# Mainboard.net
KiCad netlist of a schematic drawn in EAGLE
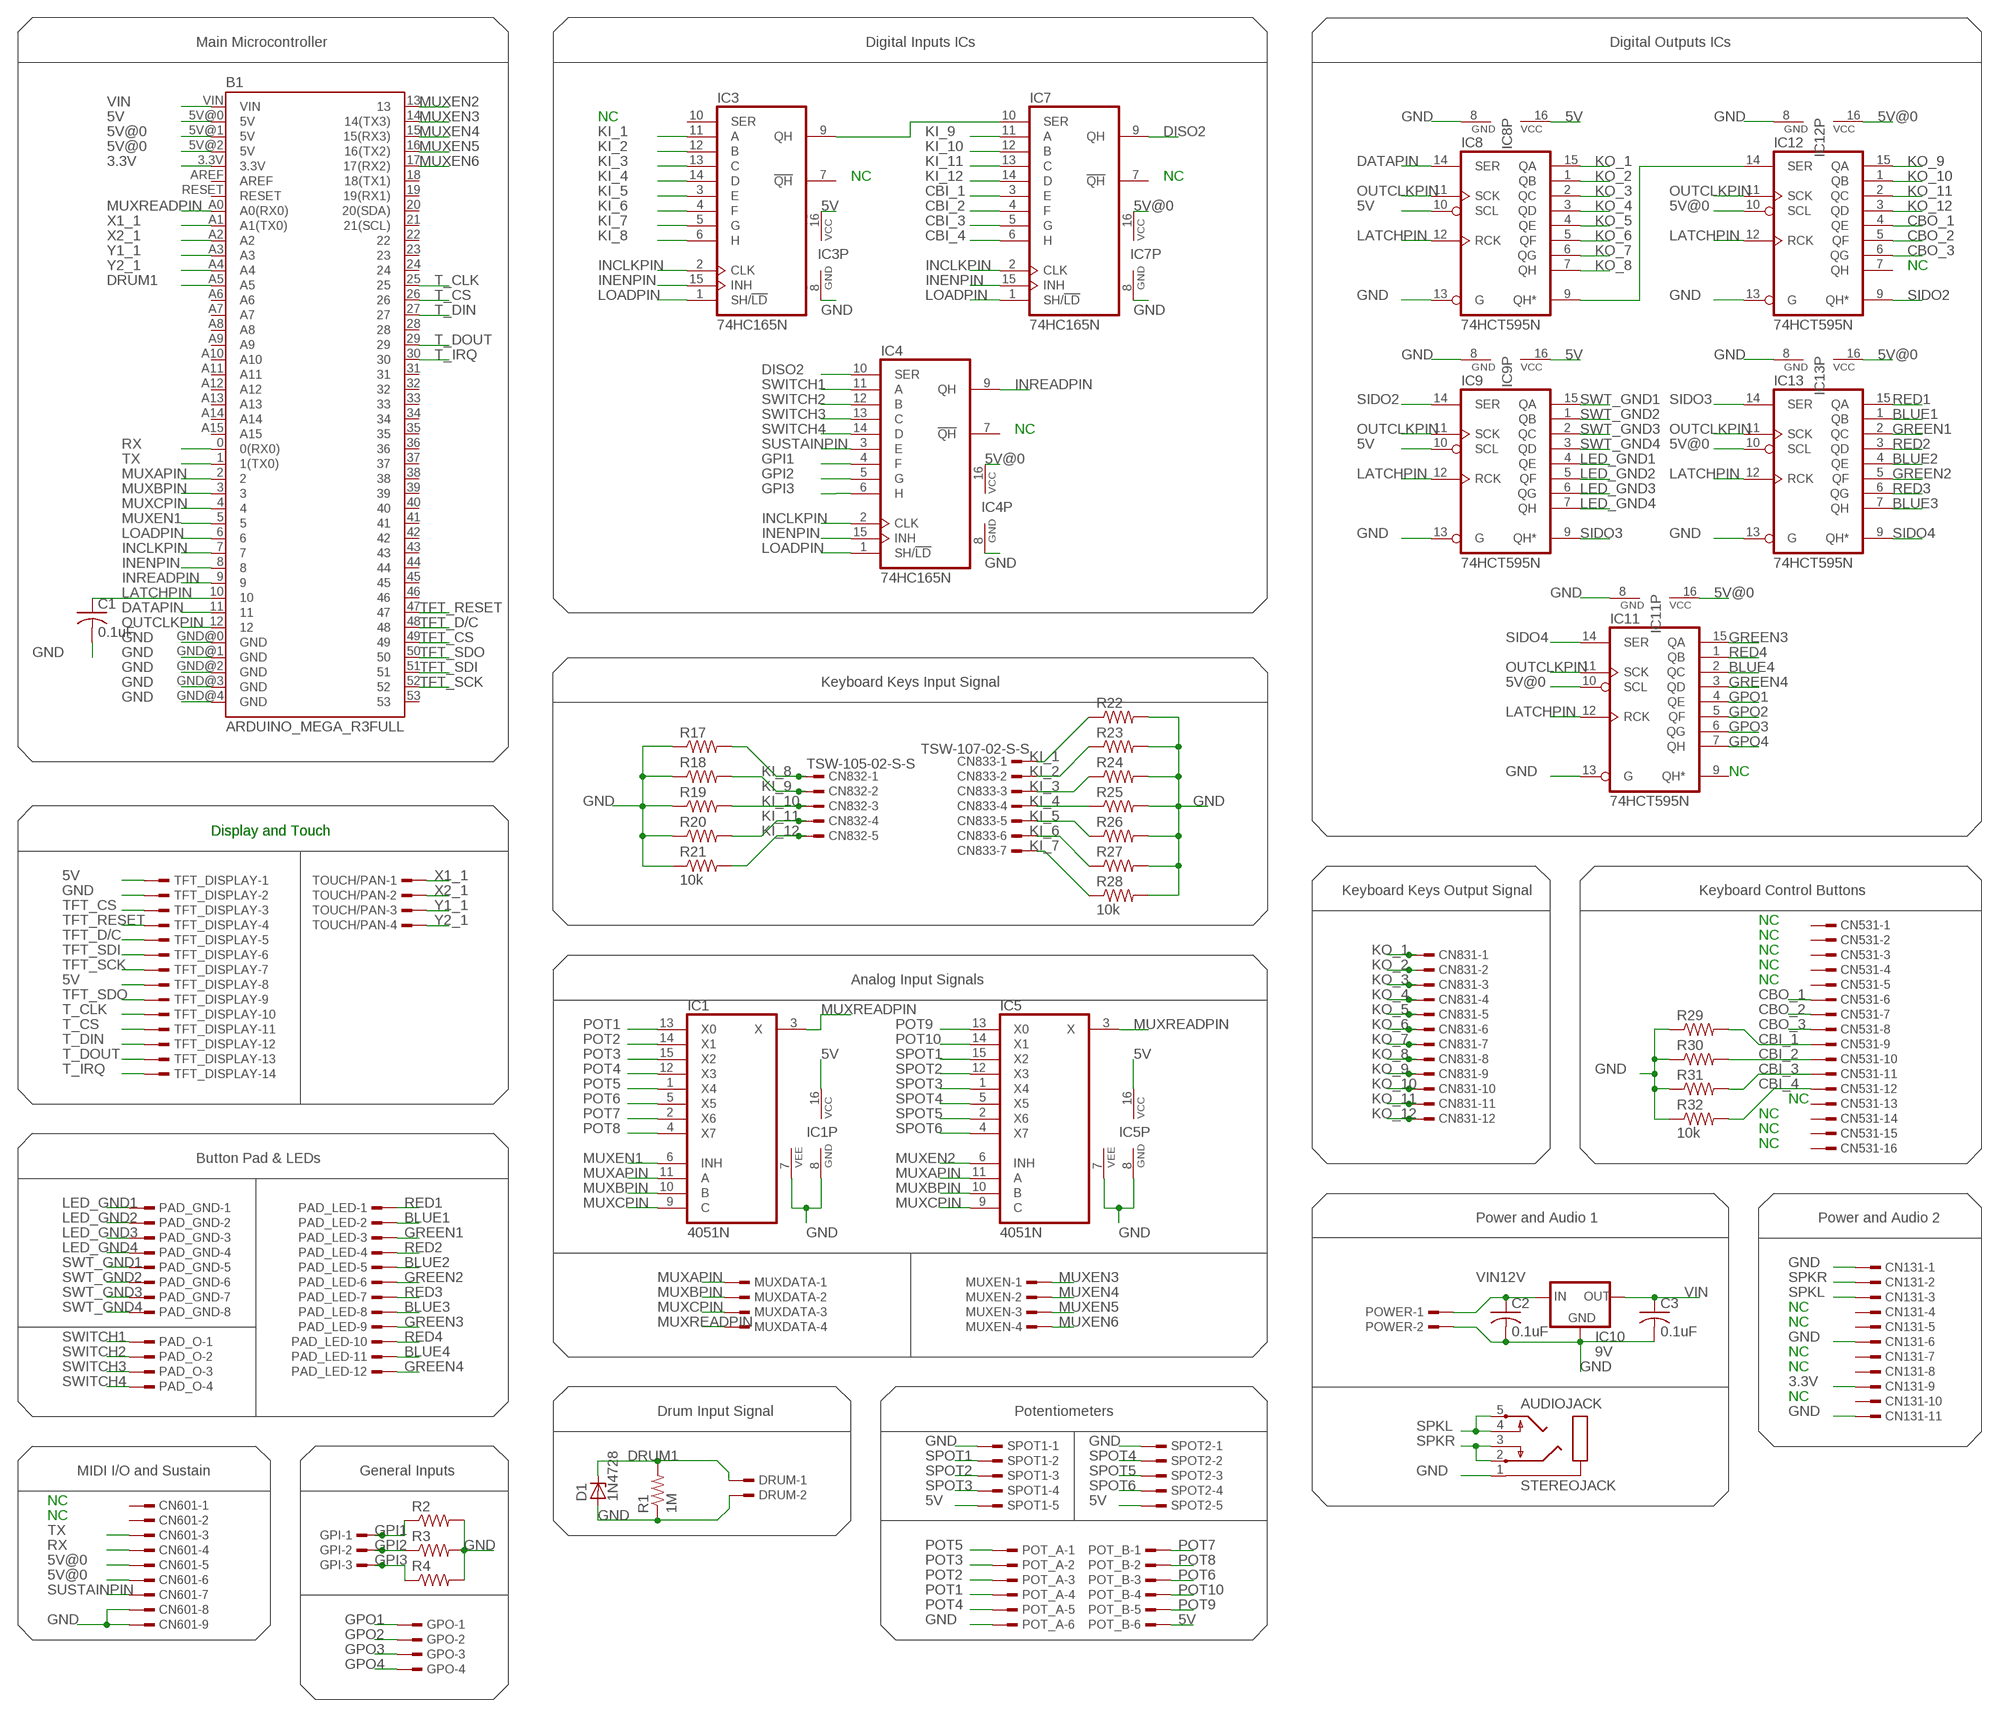
[diagram p0: schematic, sheet 1]

(export (version "E")
  (design (tool "Eeschema 10.0.6"))
  (components
    (comp (ref "AUDIOJACK")
      (value "STEREOJACK")
      (footprint "eagle-import:STX3100")
      (libsource (lib "eagle-import") (part "STEREOJACK"))
    )
    (comp (ref "B1")
      (value "ARDUINO_MEGA_R3FULL")
      (footprint "eagle-import:ARDUINO_MEGA")
      (libsource (lib "eagle-import") (part "ARDUINO_MEGA_R3FULL"))
    )
    (comp (ref "C1")
      (value "0.1uF")
      (footprint "eagle-import:C050-075X075")
      (libsource (lib "eagle-import") (part "C-US050-075X075"))
    )
    (comp (ref "C2")
      (value "0.1uF")
      (footprint "eagle-import:C050-075X075")
      (libsource (lib "eagle-import") (part "C-US050-075X075"))
    )
    (comp (ref "C3")
      (value "0.1uF")
      (footprint "eagle-import:C050-075X075")
      (libsource (lib "eagle-import") (part "C-US050-075X075"))
    )
    (comp (ref "CN131")
      (value "TSW-111-02-S-S")
      (footprint "eagle-import:TSW-111-02-S-S")
      (libsource (lib "eagle-import") (part "TSW-111-02-S-S"))
    )
    (comp (ref "CN531")
      (value "TSW-116-02-S-S")
      (footprint "eagle-import:TSW-116-02-S-S")
      (libsource (lib "eagle-import") (part "TSW-116-02-S-S"))
    )
    (comp (ref "CN601")
      (value "TSW-109-02-S-S")
      (footprint "eagle-import:TSW-109-02-S-S")
      (libsource (lib "eagle-import") (part "TSW-109-02-S-S"))
    )
    (comp (ref "CN831")
      (value "TSW-112-02-S-S")
      (footprint "eagle-import:TSW-112-02-S-S")
      (libsource (lib "eagle-import") (part "TSW-112-02-S-S"))
    )
    (comp (ref "CN832")
      (value "TSW-105-02-S-S")
      (footprint "eagle-import:TSW-105-02-S-S")
      (libsource (lib "eagle-import") (part "TSW-105-02-S-S"))
    )
    (comp (ref "CN833")
      (value "TSW-107-02-S-S")
      (footprint "eagle-import:TSW-107-02-S-S")
      (libsource (lib "eagle-import") (part "TSW-107-02-S-S"))
    )
    (comp (ref "D1")
      (value "1N4728")
      (footprint "eagle-import:DO41Z10")
      (libsource (lib "eagle-import") (part "1N4728"))
    )
    (comp (ref "DRUM")
      (value "TSW-102-02-S-S")
      (footprint "eagle-import:TSW-102-02-S-S")
      (libsource (lib "eagle-import") (part "TSW-102-02-S-S"))
    )
    (comp (ref "GPI")
      (value "TSW-103-02-S-S")
      (footprint "eagle-import:TSW-103-02-S-S")
      (libsource (lib "eagle-import") (part "TSW-103-02-S-S"))
    )
    (comp (ref "GPO")
      (value "TSW-104-02-S-S")
      (footprint "eagle-import:TSW-104-02-S-S")
      (libsource (lib "eagle-import") (part "TSW-104-02-S-S"))
    )
    (comp (ref "IC1")
      (value "4051N")
      (footprint "eagle-import:DIL16")
      (libsource (lib "eagle-import") (part "4051N"))
    )
    (comp (ref "IC3")
      (value "74HC165N")
      (footprint "eagle-import:DIL16")
      (libsource (lib "eagle-import") (part "74165NHC"))
    )
    (comp (ref "IC4")
      (value "74HC165N")
      (footprint "eagle-import:DIL16")
      (libsource (lib "eagle-import") (part "74165NHC"))
    )
    (comp (ref "IC5")
      (value "4051N")
      (footprint "eagle-import:DIL16")
      (libsource (lib "eagle-import") (part "4051N"))
    )
    (comp (ref "IC7")
      (value "74HC165N")
      (footprint "eagle-import:DIL16")
      (libsource (lib "eagle-import") (part "74165NHC"))
    )
    (comp (ref "IC8")
      (value "74HCT595N")
      (footprint "eagle-import:DIL16")
      (libsource (lib "eagle-import") (part "74595NHCT"))
    )
    (comp (ref "IC9")
      (value "74HCT595N")
      (footprint "eagle-import:DIL16")
      (libsource (lib "eagle-import") (part "74595NHCT"))
    )
    (comp (ref "IC10")
      (value "9V")
      (footprint "eagle-import:78XXL")
      (libsource (lib "eagle-import") (part "78XXL"))
    )
    (comp (ref "IC11")
      (value "74HCT595N")
      (footprint "eagle-import:DIL16")
      (libsource (lib "eagle-import") (part "74595NHCT"))
    )
    (comp (ref "IC12")
      (value "74HCT595N")
      (footprint "eagle-import:DIL16")
      (libsource (lib "eagle-import") (part "74595NHCT"))
    )
    (comp (ref "IC13")
      (value "74HCT595N")
      (footprint "eagle-import:DIL16")
      (libsource (lib "eagle-import") (part "74595NHCT"))
    )
    (comp (ref "MUXDATA")
      (value "TSW-104-02-S-S")
      (footprint "eagle-import:TSW-104-02-S-S")
      (libsource (lib "eagle-import") (part "TSW-104-02-S-S"))
    )
    (comp (ref "MUXEN")
      (value "TSW-104-02-S-S")
      (footprint "eagle-import:TSW-104-02-S-S")
      (libsource (lib "eagle-import") (part "TSW-104-02-S-S"))
    )
    (comp (ref "PAD_GND")
      (value "TSW-108-02-S-S")
      (footprint "eagle-import:TSW-108-02-S-S")
      (libsource (lib "eagle-import") (part "TSW-108-02-S-S"))
    )
    (comp (ref "PAD_LED")
      (value "TSW-112-02-S-S")
      (footprint "eagle-import:TSW-112-02-S-S")
      (libsource (lib "eagle-import") (part "TSW-112-02-S-S"))
    )
    (comp (ref "PAD_O")
      (value "TSW-104-02-S-S")
      (footprint "eagle-import:TSW-104-02-S-S")
      (libsource (lib "eagle-import") (part "TSW-104-02-S-S"))
    )
    (comp (ref "POT_A")
      (value "TSW-106-02-S-S")
      (footprint "eagle-import:TSW-106-02-S-S")
      (libsource (lib "eagle-import") (part "TSW-106-02-S-S"))
    )
    (comp (ref "POT_B")
      (value "TSW-106-02-S-S")
      (footprint "eagle-import:TSW-106-02-S-S")
      (libsource (lib "eagle-import") (part "TSW-106-02-S-S"))
    )
    (comp (ref "POWER")
      (value "TSW-102-02-S-S")
      (footprint "eagle-import:TSW-102-02-S-S")
      (libsource (lib "eagle-import") (part "TSW-102-02-S-S"))
    )
    (comp (ref "R1")
      (value "1M")
      (footprint "eagle-import:0309_12")
      (libsource (lib "eagle-import") (part "R-US_0309/12"))
    )
    (comp (ref "R2")
      (value "10k")
      (footprint "eagle-import:0309_12")
      (libsource (lib "eagle-import") (part "R-US_0309/12"))
    )
    (comp (ref "R3")
      (value "10k")
      (footprint "eagle-import:0309_12")
      (libsource (lib "eagle-import") (part "R-US_0309/12"))
    )
    (comp (ref "R4")
      (value "10k")
      (footprint "eagle-import:0309_12")
      (libsource (lib "eagle-import") (part "R-US_0309/12"))
    )
    (comp (ref "R17")
      (value "10k")
      (footprint "eagle-import:0309_12")
      (libsource (lib "eagle-import") (part "R-US_0309/12"))
    )
    (comp (ref "R18")
      (value "10k")
      (footprint "eagle-import:0309_12")
      (libsource (lib "eagle-import") (part "R-US_0309/12"))
    )
    (comp (ref "R19")
      (value "10k")
      (footprint "eagle-import:0309_12")
      (libsource (lib "eagle-import") (part "R-US_0309/12"))
    )
    (comp (ref "R20")
      (value "10k")
      (footprint "eagle-import:0309_12")
      (libsource (lib "eagle-import") (part "R-US_0309/12"))
    )
    (comp (ref "R21")
      (value "10k")
      (footprint "eagle-import:0309_12")
      (libsource (lib "eagle-import") (part "R-US_0309/12"))
    )
    (comp (ref "R22")
      (value "10k")
      (footprint "eagle-import:0309_12")
      (libsource (lib "eagle-import") (part "R-US_0309/12"))
    )
    (comp (ref "R23")
      (value "10k")
      (footprint "eagle-import:0309_12")
      (libsource (lib "eagle-import") (part "R-US_0309/12"))
    )
    (comp (ref "R24")
      (value "10k")
      (footprint "eagle-import:0309_12")
      (libsource (lib "eagle-import") (part "R-US_0309/12"))
    )
    (comp (ref "R25")
      (value "10k")
      (footprint "eagle-import:0309_12")
      (libsource (lib "eagle-import") (part "R-US_0309/12"))
    )
    (comp (ref "R26")
      (value "10k")
      (footprint "eagle-import:0309_12")
      (libsource (lib "eagle-import") (part "R-US_0309/12"))
    )
    (comp (ref "R27")
      (value "10k")
      (footprint "eagle-import:0309_12")
      (libsource (lib "eagle-import") (part "R-US_0309/12"))
    )
    (comp (ref "R28")
      (value "10k")
      (footprint "eagle-import:0309_12")
      (libsource (lib "eagle-import") (part "R-US_0309/12"))
    )
    (comp (ref "R29")
      (value "10k")
      (footprint "eagle-import:0309_12")
      (libsource (lib "eagle-import") (part "R-US_0309/12"))
    )
    (comp (ref "R30")
      (value "10k")
      (footprint "eagle-import:0309_12")
      (libsource (lib "eagle-import") (part "R-US_0309/12"))
    )
    (comp (ref "R31")
      (value "10k")
      (footprint "eagle-import:0309_12")
      (libsource (lib "eagle-import") (part "R-US_0309/12"))
    )
    (comp (ref "R32")
      (value "10k")
      (footprint "eagle-import:0309_12")
      (libsource (lib "eagle-import") (part "R-US_0309/12"))
    )
    (comp (ref "SPOT1")
      (value "TSW-105-02-S-S")
      (footprint "eagle-import:TSW-105-02-S-S")
      (libsource (lib "eagle-import") (part "TSW-105-02-S-S"))
    )
    (comp (ref "SPOT2")
      (value "TSW-105-02-S-S")
      (footprint "eagle-import:TSW-105-02-S-S")
      (libsource (lib "eagle-import") (part "TSW-105-02-S-S"))
    )
    (comp (ref "TFT_DISPLAY")
      (value "TSW-114-02-S-S")
      (footprint "eagle-import:TSW-114-02-S-S")
      (libsource (lib "eagle-import") (part "TSW-114-02-S-S"))
    )
    (comp (ref "TOUCH/PAN")
      (value "TSW-104-02-S-S")
      (footprint "eagle-import:TSW-104-02-S-S")
      (libsource (lib "eagle-import") (part "TSW-104-02-S-S"))
    )
  )
  (nets
    (net (code "1") (name "/3.3V") (class "Default")
      (node (ref "B1") (pin "3.3V") (pinfunction "3.3V_3.3V") (pintype "bidirectional"))
      (node (ref "CN131") (pin "9") (pinfunction "1_9") (pintype "passive"))
    )
    (net (code "2") (name "/5V") (class "Default")
      (node (ref "B1") (pin "5V@0") (pinfunction "5V_5V@0") (pintype "bidirectional"))
      (node (ref "IC1") (pin "16") (pinfunction "VCC_16") (pintype "power_in"))
      (node (ref "IC3") (pin "16") (pinfunction "VCC_16") (pintype "power_in"))
      (node (ref "IC5") (pin "16") (pinfunction "VCC_16") (pintype "power_in"))
      (node (ref "IC8") (pin "10") (pinfunction "SCL_10") (pintype "input"))
      (node (ref "IC8") (pin "16") (pinfunction "VCC_16") (pintype "power_in"))
      (node (ref "IC9") (pin "10") (pinfunction "SCL_10") (pintype "input"))
      (node (ref "IC9") (pin "16") (pinfunction "VCC_16") (pintype "power_in"))
      (node (ref "POT_B") (pin "6") (pinfunction "1_6") (pintype "passive"))
      (node (ref "SPOT1") (pin "5") (pinfunction "1_5") (pintype "passive"))
      (node (ref "SPOT2") (pin "5") (pinfunction "1_5") (pintype "passive"))
      (node (ref "TFT_DISPLAY") (pin "1") (pinfunction "1_1") (pintype "passive"))
      (node (ref "TFT_DISPLAY") (pin "8") (pinfunction "1_8") (pintype "passive"))
    )
    (net (code "3") (name "/5V@0") (class "Default")
      (node (ref "B1") (pin "5V@1") (pinfunction "5V_5V@1") (pintype "bidirectional"))
      (node (ref "B1") (pin "5V@2") (pinfunction "5V_5V@2") (pintype "bidirectional"))
      (node (ref "CN601") (pin "5") (pinfunction "1_5") (pintype "passive"))
      (node (ref "CN601") (pin "6") (pinfunction "1_6") (pintype "passive"))
      (node (ref "IC11") (pin "10") (pinfunction "SCL_10") (pintype "input"))
      (node (ref "IC11") (pin "16") (pinfunction "VCC_16") (pintype "power_in"))
      (node (ref "IC12") (pin "10") (pinfunction "SCL_10") (pintype "input"))
      (node (ref "IC12") (pin "16") (pinfunction "VCC_16") (pintype "power_in"))
      (node (ref "IC13") (pin "10") (pinfunction "SCL_10") (pintype "input"))
      (node (ref "IC13") (pin "16") (pinfunction "VCC_16") (pintype "power_in"))
      (node (ref "IC4") (pin "16") (pinfunction "VCC_16") (pintype "power_in"))
      (node (ref "IC7") (pin "16") (pinfunction "VCC_16") (pintype "power_in"))
    )
    (net (code "4") (name "/BLUE1") (class "Default")
      (node (ref "IC13") (pin "1") (pinfunction "QB_1") (pintype "tri_state"))
      (node (ref "PAD_LED") (pin "2") (pinfunction "1_2") (pintype "passive"))
    )
    (net (code "5") (name "/BLUE2") (class "Default")
      (node (ref "IC13") (pin "4") (pinfunction "QE_4") (pintype "tri_state"))
      (node (ref "PAD_LED") (pin "5") (pinfunction "1_5") (pintype "passive"))
    )
    (net (code "6") (name "/BLUE3") (class "Default")
      (node (ref "IC13") (pin "7") (pinfunction "QH_7") (pintype "tri_state"))
      (node (ref "PAD_LED") (pin "8") (pinfunction "1_8") (pintype "passive"))
    )
    (net (code "7") (name "/BLUE4") (class "Default")
      (node (ref "IC11") (pin "2") (pinfunction "QC_2") (pintype "tri_state"))
      (node (ref "PAD_LED") (pin "11") (pinfunction "1_11") (pintype "passive"))
    )
    (net (code "8") (name "/CBI_1") (class "Default")
      (node (ref "CN531") (pin "9") (pinfunction "1_9") (pintype "passive"))
      (node (ref "IC7") (pin "3") (pinfunction "E_3") (pintype "input"))
      (node (ref "R29") (pin "2") (pinfunction "2_2") (pintype "passive"))
    )
    (net (code "9") (name "/CBI_2") (class "Default")
      (node (ref "CN531") (pin "10") (pinfunction "1_10") (pintype "passive"))
      (node (ref "IC7") (pin "4") (pinfunction "F_4") (pintype "input"))
      (node (ref "R30") (pin "2") (pinfunction "2_2") (pintype "passive"))
    )
    (net (code "10") (name "/CBI_3") (class "Default")
      (node (ref "CN531") (pin "11") (pinfunction "1_11") (pintype "passive"))
      (node (ref "IC7") (pin "5") (pinfunction "G_5") (pintype "input"))
      (node (ref "R31") (pin "2") (pinfunction "2_2") (pintype "passive"))
    )
    (net (code "11") (name "/CBI_4") (class "Default")
      (node (ref "CN531") (pin "12") (pinfunction "1_12") (pintype "passive"))
      (node (ref "IC7") (pin "6") (pinfunction "H_6") (pintype "input"))
      (node (ref "R32") (pin "2") (pinfunction "2_2") (pintype "passive"))
    )
    (net (code "12") (name "/CBO_1") (class "Default")
      (node (ref "CN531") (pin "6") (pinfunction "1_6") (pintype "passive"))
      (node (ref "IC12") (pin "4") (pinfunction "QE_4") (pintype "tri_state"))
    )
    (net (code "13") (name "/CBO_2") (class "Default")
      (node (ref "CN531") (pin "7") (pinfunction "1_7") (pintype "passive"))
      (node (ref "IC12") (pin "5") (pinfunction "QF_5") (pintype "tri_state"))
    )
    (net (code "14") (name "/CBO_3") (class "Default")
      (node (ref "CN531") (pin "8") (pinfunction "1_8") (pintype "passive"))
      (node (ref "IC12") (pin "6") (pinfunction "QG_6") (pintype "tri_state"))
    )
    (net (code "15") (name "/DATAPIN") (class "Default")
      (node (ref "B1") (pin "11") (pinfunction "11_11") (pintype "bidirectional"))
      (node (ref "IC8") (pin "14") (pinfunction "SER_14") (pintype "input"))
    )
    (net (code "16") (name "/DISO2") (class "Default")
      (node (ref "IC4") (pin "10") (pinfunction "SER_10") (pintype "input"))
      (node (ref "IC7") (pin "9") (pinfunction "QH_9") (pintype "output"))
    )
    (net (code "17") (name "/DRUM1") (class "Default")
      (node (ref "B1") (pin "A5") (pinfunction "A5_A5") (pintype "bidirectional"))
      (node (ref "D1") (pin "C") (pinfunction "C_C") (pintype "passive"))
      (node (ref "DRUM") (pin "1") (pinfunction "1_1") (pintype "passive"))
      (node (ref "R1") (pin "2") (pinfunction "2_2") (pintype "passive"))
    )
    (net (code "18") (name "/GND") (class "Default")
      (node (ref "AUDIOJACK") (pin "1") (pinfunction "1_1") (pintype "passive"))
      (node (ref "B1") (pin "GND@0") (pinfunction "GND_GND@0") (pintype "bidirectional"))
      (node (ref "B1") (pin "GND@1") (pinfunction "GND_GND@1") (pintype "bidirectional"))
      (node (ref "B1") (pin "GND@2") (pinfunction "GND_GND@2") (pintype "bidirectional"))
      (node (ref "B1") (pin "GND@3") (pinfunction "GND_GND@3") (pintype "bidirectional"))
      (node (ref "B1") (pin "GND@4") (pinfunction "GND_GND@4") (pintype "bidirectional"))
      (node (ref "C1") (pin "2") (pinfunction "2_2") (pintype "passive"))
      (node (ref "C2") (pin "2") (pinfunction "2_2") (pintype "passive"))
      (node (ref "C3") (pin "2") (pinfunction "2_2") (pintype "passive"))
      (node (ref "CN131") (pin "1") (pinfunction "1_1") (pintype "passive"))
      (node (ref "CN131") (pin "11") (pinfunction "1_11") (pintype "passive"))
      (node (ref "CN131") (pin "6") (pinfunction "1_6") (pintype "passive"))
      (node (ref "CN601") (pin "8") (pinfunction "1_8") (pintype "passive"))
      (node (ref "CN601") (pin "9") (pinfunction "1_9") (pintype "passive"))
      (node (ref "D1") (pin "A") (pinfunction "A_A") (pintype "passive"))
      (node (ref "DRUM") (pin "2") (pinfunction "1_2") (pintype "passive"))
      (node (ref "IC1") (pin "7") (pinfunction "VEE_7") (pintype "power_in"))
      (node (ref "IC1") (pin "8") (pinfunction "GND_8") (pintype "power_in"))
      (node (ref "IC10") (pin "GND") (pinfunction "GND_GND") (pintype "input"))
      (node (ref "IC11") (pin "13") (pinfunction "G_13") (pintype "input"))
      (node (ref "IC11") (pin "8") (pinfunction "GND_8") (pintype "power_in"))
      (node (ref "IC12") (pin "13") (pinfunction "G_13") (pintype "input"))
      (node (ref "IC12") (pin "8") (pinfunction "GND_8") (pintype "power_in"))
      (node (ref "IC13") (pin "13") (pinfunction "G_13") (pintype "input"))
      (node (ref "IC13") (pin "8") (pinfunction "GND_8") (pintype "power_in"))
      (node (ref "IC3") (pin "8") (pinfunction "GND_8") (pintype "power_in"))
      (node (ref "IC4") (pin "8") (pinfunction "GND_8") (pintype "power_in"))
      (node (ref "IC5") (pin "7") (pinfunction "VEE_7") (pintype "power_in"))
      (node (ref "IC5") (pin "8") (pinfunction "GND_8") (pintype "power_in"))
      (node (ref "IC7") (pin "8") (pinfunction "GND_8") (pintype "power_in"))
      (node (ref "IC8") (pin "13") (pinfunction "G_13") (pintype "input"))
      (node (ref "IC8") (pin "8") (pinfunction "GND_8") (pintype "power_in"))
      (node (ref "IC9") (pin "13") (pinfunction "G_13") (pintype "input"))
      (node (ref "IC9") (pin "8") (pinfunction "GND_8") (pintype "power_in"))
      (node (ref "POT_A") (pin "6") (pinfunction "1_6") (pintype "passive"))
      (node (ref "POWER") (pin "2") (pinfunction "1_2") (pintype "passive"))
      (node (ref "R1") (pin "1") (pinfunction "1_1") (pintype "passive"))
      (node (ref "R17") (pin "1") (pinfunction "1_1") (pintype "passive"))
      (node (ref "R18") (pin "1") (pinfunction "1_1") (pintype "passive"))
      (node (ref "R19") (pin "1") (pinfunction "1_1") (pintype "passive"))
      (node (ref "R2") (pin "2") (pinfunction "2_2") (pintype "passive"))
      (node (ref "R20") (pin "1") (pinfunction "1_1") (pintype "passive"))
      (node (ref "R21") (pin "1") (pinfunction "1_1") (pintype "passive"))
      (node (ref "R22") (pin "2") (pinfunction "2_2") (pintype "passive"))
      (node (ref "R23") (pin "2") (pinfunction "2_2") (pintype "passive"))
      (node (ref "R24") (pin "2") (pinfunction "2_2") (pintype "passive"))
      (node (ref "R25") (pin "2") (pinfunction "2_2") (pintype "passive"))
      (node (ref "R26") (pin "2") (pinfunction "2_2") (pintype "passive"))
      (node (ref "R27") (pin "2") (pinfunction "2_2") (pintype "passive"))
      (node (ref "R28") (pin "2") (pinfunction "2_2") (pintype "passive"))
      (node (ref "R29") (pin "1") (pinfunction "1_1") (pintype "passive"))
      (node (ref "R3") (pin "2") (pinfunction "2_2") (pintype "passive"))
      (node (ref "R30") (pin "1") (pinfunction "1_1") (pintype "passive"))
      (node (ref "R31") (pin "1") (pinfunction "1_1") (pintype "passive"))
      (node (ref "R32") (pin "1") (pinfunction "1_1") (pintype "passive"))
      (node (ref "R4") (pin "2") (pinfunction "2_2") (pintype "passive"))
      (node (ref "SPOT1") (pin "1") (pinfunction "1_1") (pintype "passive"))
      (node (ref "SPOT2") (pin "1") (pinfunction "1_1") (pintype "passive"))
      (node (ref "TFT_DISPLAY") (pin "2") (pinfunction "1_2") (pintype "passive"))
    )
    (net (code "19") (name "/GPI1") (class "Default")
      (node (ref "GPI") (pin "1") (pinfunction "1_1") (pintype "passive"))
      (node (ref "IC4") (pin "4") (pinfunction "F_4") (pintype "input"))
      (node (ref "R2") (pin "1") (pinfunction "1_1") (pintype "passive"))
    )
    (net (code "20") (name "/GPI2") (class "Default")
      (node (ref "GPI") (pin "2") (pinfunction "1_2") (pintype "passive"))
      (node (ref "IC4") (pin "5") (pinfunction "G_5") (pintype "input"))
      (node (ref "R3") (pin "1") (pinfunction "1_1") (pintype "passive"))
    )
    (net (code "21") (name "/GPI3") (class "Default")
      (node (ref "GPI") (pin "3") (pinfunction "1_3") (pintype "passive"))
      (node (ref "IC4") (pin "6") (pinfunction "H_6") (pintype "input"))
      (node (ref "R4") (pin "1") (pinfunction "1_1") (pintype "passive"))
    )
    (net (code "22") (name "/GPO1") (class "Default")
      (node (ref "GPO") (pin "1") (pinfunction "1_1") (pintype "passive"))
      (node (ref "IC11") (pin "4") (pinfunction "QE_4") (pintype "tri_state"))
    )
    (net (code "23") (name "/GPO2") (class "Default")
      (node (ref "GPO") (pin "2") (pinfunction "1_2") (pintype "passive"))
      (node (ref "IC11") (pin "5") (pinfunction "QF_5") (pintype "tri_state"))
    )
    (net (code "24") (name "/GPO3") (class "Default")
      (node (ref "GPO") (pin "3") (pinfunction "1_3") (pintype "passive"))
      (node (ref "IC11") (pin "6") (pinfunction "QG_6") (pintype "tri_state"))
    )
    (net (code "25") (name "/GPO4") (class "Default")
      (node (ref "GPO") (pin "4") (pinfunction "1_4") (pintype "passive"))
      (node (ref "IC11") (pin "7") (pinfunction "QH_7") (pintype "tri_state"))
    )
    (net (code "26") (name "/GREEN1") (class "Default")
      (node (ref "IC13") (pin "2") (pinfunction "QC_2") (pintype "tri_state"))
      (node (ref "PAD_LED") (pin "3") (pinfunction "1_3") (pintype "passive"))
    )
    (net (code "27") (name "/GREEN2") (class "Default")
      (node (ref "IC13") (pin "5") (pinfunction "QF_5") (pintype "tri_state"))
      (node (ref "PAD_LED") (pin "6") (pinfunction "1_6") (pintype "passive"))
    )
    (net (code "28") (name "/GREEN3") (class "Default")
      (node (ref "IC11") (pin "15") (pinfunction "QA_15") (pintype "tri_state"))
      (node (ref "PAD_LED") (pin "9") (pinfunction "1_9") (pintype "passive"))
    )
    (net (code "29") (name "/GREEN4") (class "Default")
      (node (ref "IC11") (pin "3") (pinfunction "QD_3") (pintype "tri_state"))
      (node (ref "PAD_LED") (pin "12") (pinfunction "1_12") (pintype "passive"))
    )
    (net (code "30") (name "/INCLKPIN") (class "Default")
      (node (ref "B1") (pin "7") (pinfunction "7_7") (pintype "bidirectional"))
      (node (ref "IC3") (pin "2") (pinfunction "CLK_2") (pintype "input"))
      (node (ref "IC4") (pin "2") (pinfunction "CLK_2") (pintype "input"))
      (node (ref "IC7") (pin "2") (pinfunction "CLK_2") (pintype "input"))
    )
    (net (code "31") (name "/INENPIN") (class "Default")
      (node (ref "B1") (pin "8") (pinfunction "8_8") (pintype "bidirectional"))
      (node (ref "IC3") (pin "15") (pinfunction "INH_15") (pintype "input"))
      (node (ref "IC4") (pin "15") (pinfunction "INH_15") (pintype "input"))
      (node (ref "IC7") (pin "15") (pinfunction "INH_15") (pintype "input"))
    )
    (net (code "32") (name "/INREADPIN") (class "Default")
      (node (ref "B1") (pin "9") (pinfunction "9_9") (pintype "bidirectional"))
      (node (ref "IC4") (pin "9") (pinfunction "QH_9") (pintype "output"))
    )
    (net (code "33") (name "/KI_1") (class "Default")
      (node (ref "CN833") (pin "1") (pinfunction "1_1") (pintype "passive"))
      (node (ref "IC3") (pin "11") (pinfunction "A_11") (pintype "input"))
      (node (ref "R22") (pin "1") (pinfunction "1_1") (pintype "passive"))
    )
    (net (code "34") (name "/KI_2") (class "Default")
      (node (ref "CN833") (pin "2") (pinfunction "1_2") (pintype "passive"))
      (node (ref "IC3") (pin "12") (pinfunction "B_12") (pintype "input"))
      (node (ref "R23") (pin "1") (pinfunction "1_1") (pintype "passive"))
    )
    (net (code "35") (name "/KI_3") (class "Default")
      (node (ref "CN833") (pin "3") (pinfunction "1_3") (pintype "passive"))
      (node (ref "IC3") (pin "13") (pinfunction "C_13") (pintype "input"))
      (node (ref "R24") (pin "1") (pinfunction "1_1") (pintype "passive"))
    )
    (net (code "36") (name "/KI_4") (class "Default")
      (node (ref "CN833") (pin "4") (pinfunction "1_4") (pintype "passive"))
      (node (ref "IC3") (pin "14") (pinfunction "D_14") (pintype "input"))
      (node (ref "R25") (pin "1") (pinfunction "1_1") (pintype "passive"))
    )
    (net (code "37") (name "/KI_5") (class "Default")
      (node (ref "CN833") (pin "5") (pinfunction "1_5") (pintype "passive"))
      (node (ref "IC3") (pin "3") (pinfunction "E_3") (pintype "input"))
      (node (ref "R26") (pin "1") (pinfunction "1_1") (pintype "passive"))
    )
    (net (code "38") (name "/KI_6") (class "Default")
      (node (ref "CN833") (pin "6") (pinfunction "1_6") (pintype "passive"))
      (node (ref "IC3") (pin "4") (pinfunction "F_4") (pintype "input"))
      (node (ref "R27") (pin "1") (pinfunction "1_1") (pintype "passive"))
    )
    (net (code "39") (name "/KI_7") (class "Default")
      (node (ref "CN833") (pin "7") (pinfunction "1_7") (pintype "passive"))
      (node (ref "IC3") (pin "5") (pinfunction "G_5") (pintype "input"))
      (node (ref "R28") (pin "1") (pinfunction "1_1") (pintype "passive"))
    )
    (net (code "40") (name "/KI_8") (class "Default")
      (node (ref "CN832") (pin "1") (pinfunction "1_1") (pintype "passive"))
      (node (ref "IC3") (pin "6") (pinfunction "H_6") (pintype "input"))
      (node (ref "R17") (pin "2") (pinfunction "2_2") (pintype "passive"))
    )
    (net (code "41") (name "/KI_9") (class "Default")
      (node (ref "CN832") (pin "2") (pinfunction "1_2") (pintype "passive"))
      (node (ref "IC7") (pin "11") (pinfunction "A_11") (pintype "input"))
      (node (ref "R18") (pin "2") (pinfunction "2_2") (pintype "passive"))
    )
    (net (code "42") (name "/KI_10") (class "Default")
      (node (ref "CN832") (pin "3") (pinfunction "1_3") (pintype "passive"))
      (node (ref "IC7") (pin "12") (pinfunction "B_12") (pintype "input"))
      (node (ref "R19") (pin "2") (pinfunction "2_2") (pintype "passive"))
    )
    (net (code "43") (name "/KI_11") (class "Default")
      (node (ref "CN832") (pin "4") (pinfunction "1_4") (pintype "passive"))
      (node (ref "IC7") (pin "13") (pinfunction "C_13") (pintype "input"))
      (node (ref "R20") (pin "2") (pinfunction "2_2") (pintype "passive"))
    )
    (net (code "44") (name "/KI_12") (class "Default")
      (node (ref "CN832") (pin "5") (pinfunction "1_5") (pintype "passive"))
      (node (ref "IC7") (pin "14") (pinfunction "D_14") (pintype "input"))
      (node (ref "R21") (pin "2") (pinfunction "2_2") (pintype "passive"))
    )
    (net (code "45") (name "/KO_1") (class "Default")
      (node (ref "CN831") (pin "1") (pinfunction "1_1") (pintype "passive"))
      (node (ref "IC8") (pin "15") (pinfunction "QA_15") (pintype "tri_state"))
    )
    (net (code "46") (name "/KO_2") (class "Default")
      (node (ref "CN831") (pin "2") (pinfunction "1_2") (pintype "passive"))
      (node (ref "IC8") (pin "1") (pinfunction "QB_1") (pintype "tri_state"))
    )
    (net (code "47") (name "/KO_3") (class "Default")
      (node (ref "CN831") (pin "3") (pinfunction "1_3") (pintype "passive"))
      (node (ref "IC8") (pin "2") (pinfunction "QC_2") (pintype "tri_state"))
    )
    (net (code "48") (name "/KO_4") (class "Default")
      (node (ref "CN831") (pin "4") (pinfunction "1_4") (pintype "passive"))
      (node (ref "IC8") (pin "3") (pinfunction "QD_3") (pintype "tri_state"))
    )
    (net (code "49") (name "/KO_5") (class "Default")
      (node (ref "CN831") (pin "5") (pinfunction "1_5") (pintype "passive"))
      (node (ref "IC8") (pin "4") (pinfunction "QE_4") (pintype "tri_state"))
    )
    (net (code "50") (name "/KO_6") (class "Default")
      (node (ref "CN831") (pin "6") (pinfunction "1_6") (pintype "passive"))
      (node (ref "IC8") (pin "5") (pinfunction "QF_5") (pintype "tri_state"))
    )
    (net (code "51") (name "/KO_7") (class "Default")
      (node (ref "CN831") (pin "7") (pinfunction "1_7") (pintype "passive"))
      (node (ref "IC8") (pin "6") (pinfunction "QG_6") (pintype "tri_state"))
    )
    (net (code "52") (name "/KO_8") (class "Default")
      (node (ref "CN831") (pin "8") (pinfunction "1_8") (pintype "passive"))
      (node (ref "IC8") (pin "7") (pinfunction "QH_7") (pintype "tri_state"))
    )
    (net (code "53") (name "/KO_9") (class "Default")
      (node (ref "CN831") (pin "9") (pinfunction "1_9") (pintype "passive"))
      (node (ref "IC12") (pin "15") (pinfunction "QA_15") (pintype "tri_state"))
    )
    (net (code "54") (name "/KO_10") (class "Default")
      (node (ref "CN831") (pin "10") (pinfunction "1_10") (pintype "passive"))
      (node (ref "IC12") (pin "1") (pinfunction "QB_1") (pintype "tri_state"))
    )
    (net (code "55") (name "/KO_11") (class "Default")
      (node (ref "CN831") (pin "11") (pinfunction "1_11") (pintype "passive"))
      (node (ref "IC12") (pin "2") (pinfunction "QC_2") (pintype "tri_state"))
    )
    (net (code "56") (name "/KO_12") (class "Default")
      (node (ref "CN831") (pin "12") (pinfunction "1_12") (pintype "passive"))
      (node (ref "IC12") (pin "3") (pinfunction "QD_3") (pintype "tri_state"))
    )
    (net (code "57") (name "/LATCHPIN") (class "Default")
      (node (ref "B1") (pin "10") (pinfunction "10_10") (pintype "bidirectional"))
      (node (ref "C1") (pin "1") (pinfunction "1_1") (pintype "passive"))
      (node (ref "IC11") (pin "12") (pinfunction "RCK_12") (pintype "input"))
      (node (ref "IC12") (pin "12") (pinfunction "RCK_12") (pintype "input"))
      (node (ref "IC13") (pin "12") (pinfunction "RCK_12") (pintype "input"))
      (node (ref "IC8") (pin "12") (pinfunction "RCK_12") (pintype "input"))
      (node (ref "IC9") (pin "12") (pinfunction "RCK_12") (pintype "input"))
    )
    (net (code "58") (name "/LED_GND1") (class "Default")
      (node (ref "IC9") (pin "4") (pinfunction "QE_4") (pintype "tri_state"))
      (node (ref "PAD_GND") (pin "1") (pinfunction "1_1") (pintype "passive"))
    )
    (net (code "59") (name "/LED_GND2") (class "Default")
      (node (ref "IC9") (pin "5") (pinfunction "QF_5") (pintype "tri_state"))
      (node (ref "PAD_GND") (pin "2") (pinfunction "1_2") (pintype "passive"))
    )
    (net (code "60") (name "/LED_GND3") (class "Default")
      (node (ref "IC9") (pin "6") (pinfunction "QG_6") (pintype "tri_state"))
      (node (ref "PAD_GND") (pin "3") (pinfunction "1_3") (pintype "passive"))
    )
    (net (code "61") (name "/LED_GND4") (class "Default")
      (node (ref "IC9") (pin "7") (pinfunction "QH_7") (pintype "tri_state"))
      (node (ref "PAD_GND") (pin "4") (pinfunction "1_4") (pintype "passive"))
    )
    (net (code "62") (name "/LOADPIN") (class "Default")
      (node (ref "B1") (pin "6") (pinfunction "6_6") (pintype "bidirectional"))
      (node (ref "IC3") (pin "1") (pinfunction "SH/~{LD}_1") (pintype "input"))
      (node (ref "IC4") (pin "1") (pinfunction "SH/~{LD}_1") (pintype "input"))
      (node (ref "IC7") (pin "1") (pinfunction "SH/~{LD}_1") (pintype "input"))
    )
    (net (code "63") (name "/MUXAPIN") (class "Default")
      (node (ref "B1") (pin "2") (pinfunction "2_2") (pintype "bidirectional"))
      (node (ref "IC1") (pin "11") (pinfunction "A_11") (pintype "input"))
      (node (ref "IC5") (pin "11") (pinfunction "A_11") (pintype "input"))
      (node (ref "MUXDATA") (pin "1") (pinfunction "1_1") (pintype "passive"))
    )
    (net (code "64") (name "/MUXBPIN") (class "Default")
      (node (ref "B1") (pin "3") (pinfunction "3_3") (pintype "bidirectional"))
      (node (ref "IC1") (pin "10") (pinfunction "B_10") (pintype "input"))
      (node (ref "IC5") (pin "10") (pinfunction "B_10") (pintype "input"))
      (node (ref "MUXDATA") (pin "2") (pinfunction "1_2") (pintype "passive"))
    )
    (net (code "65") (name "/MUXCPIN") (class "Default")
      (node (ref "B1") (pin "4") (pinfunction "4_4") (pintype "bidirectional"))
      (node (ref "IC1") (pin "9") (pinfunction "C_9") (pintype "input"))
      (node (ref "IC5") (pin "9") (pinfunction "C_9") (pintype "input"))
      (node (ref "MUXDATA") (pin "3") (pinfunction "1_3") (pintype "passive"))
    )
    (net (code "66") (name "/MUXEN1") (class "Default")
      (node (ref "B1") (pin "5") (pinfunction "5_5") (pintype "bidirectional"))
      (node (ref "IC1") (pin "6") (pinfunction "INH_6") (pintype "input"))
    )
    (net (code "67") (name "/MUXEN2") (class "Default")
      (node (ref "B1") (pin "13") (pinfunction "13_13") (pintype "bidirectional"))
      (node (ref "IC5") (pin "6") (pinfunction "INH_6") (pintype "input"))
    )
    (net (code "68") (name "/MUXEN3") (class "Default")
      (node (ref "B1") (pin "14") (pinfunction "14(TX3)_14") (pintype "bidirectional"))
      (node (ref "MUXEN") (pin "1") (pinfunction "1_1") (pintype "passive"))
    )
    (net (code "69") (name "/MUXEN4") (class "Default")
      (node (ref "B1") (pin "15") (pinfunction "15(RX3)_15") (pintype "bidirectional"))
      (node (ref "MUXEN") (pin "2") (pinfunction "1_2") (pintype "passive"))
    )
    (net (code "70") (name "/MUXEN5") (class "Default")
      (node (ref "B1") (pin "16") (pinfunction "16(TX2)_16") (pintype "bidirectional"))
      (node (ref "MUXEN") (pin "3") (pinfunction "1_3") (pintype "passive"))
    )
    (net (code "71") (name "/MUXEN6") (class "Default")
      (node (ref "B1") (pin "17") (pinfunction "17(RX2)_17") (pintype "bidirectional"))
      (node (ref "MUXEN") (pin "4") (pinfunction "1_4") (pintype "passive"))
    )
    (net (code "72") (name "/MUXREADPIN") (class "Default")
      (node (ref "B1") (pin "A0") (pinfunction "A0(RX0)_A0") (pintype "bidirectional"))
      (node (ref "IC1") (pin "3") (pinfunction "X_3") (pintype "bidirectional"))
      (node (ref "IC5") (pin "3") (pinfunction "X_3") (pintype "bidirectional"))
      (node (ref "MUXDATA") (pin "4") (pinfunction "1_4") (pintype "passive"))
    )
    (net (code "73") (name "/OUTCLKPIN") (class "Default")
      (node (ref "B1") (pin "12") (pinfunction "12_12") (pintype "bidirectional"))
      (node (ref "IC11") (pin "11") (pinfunction "SCK_11") (pintype "input"))
      (node (ref "IC12") (pin "11") (pinfunction "SCK_11") (pintype "input"))
      (node (ref "IC13") (pin "11") (pinfunction "SCK_11") (pintype "input"))
      (node (ref "IC8") (pin "11") (pinfunction "SCK_11") (pintype "input"))
      (node (ref "IC9") (pin "11") (pinfunction "SCK_11") (pintype "input"))
    )
    (net (code "74") (name "/POT1") (class "Default")
      (node (ref "IC1") (pin "13") (pinfunction "X0_13") (pintype "bidirectional"))
      (node (ref "POT_A") (pin "4") (pinfunction "1_4") (pintype "passive"))
    )
    (net (code "75") (name "/POT2") (class "Default")
      (node (ref "IC1") (pin "14") (pinfunction "X1_14") (pintype "bidirectional"))
      (node (ref "POT_A") (pin "3") (pinfunction "1_3") (pintype "passive"))
    )
    (net (code "76") (name "/POT3") (class "Default")
      (node (ref "IC1") (pin "15") (pinfunction "X2_15") (pintype "bidirectional"))
      (node (ref "POT_A") (pin "2") (pinfunction "1_2") (pintype "passive"))
    )
    (net (code "77") (name "/POT4") (class "Default")
      (node (ref "IC1") (pin "12") (pinfunction "X3_12") (pintype "bidirectional"))
      (node (ref "POT_A") (pin "5") (pinfunction "1_5") (pintype "passive"))
    )
    (net (code "78") (name "/POT5") (class "Default")
      (node (ref "IC1") (pin "1") (pinfunction "X4_1") (pintype "bidirectional"))
      (node (ref "POT_A") (pin "1") (pinfunction "1_1") (pintype "passive"))
    )
    (net (code "79") (name "/POT6") (class "Default")
      (node (ref "IC1") (pin "5") (pinfunction "X5_5") (pintype "bidirectional"))
      (node (ref "POT_B") (pin "3") (pinfunction "1_3") (pintype "passive"))
    )
    (net (code "80") (name "/POT7") (class "Default")
      (node (ref "IC1") (pin "2") (pinfunction "X6_2") (pintype "bidirectional"))
      (node (ref "POT_B") (pin "1") (pinfunction "1_1") (pintype "passive"))
    )
    (net (code "81") (name "/POT8") (class "Default")
      (node (ref "IC1") (pin "4") (pinfunction "X7_4") (pintype "bidirectional"))
      (node (ref "POT_B") (pin "2") (pinfunction "1_2") (pintype "passive"))
    )
    (net (code "82") (name "/POT9") (class "Default")
      (node (ref "IC5") (pin "13") (pinfunction "X0_13") (pintype "bidirectional"))
      (node (ref "POT_B") (pin "5") (pinfunction "1_5") (pintype "passive"))
    )
    (net (code "83") (name "/POT10") (class "Default")
      (node (ref "IC5") (pin "14") (pinfunction "X1_14") (pintype "bidirectional"))
      (node (ref "POT_B") (pin "4") (pinfunction "1_4") (pintype "passive"))
    )
    (net (code "84") (name "/RED1") (class "Default")
      (node (ref "IC13") (pin "15") (pinfunction "QA_15") (pintype "tri_state"))
      (node (ref "PAD_LED") (pin "1") (pinfunction "1_1") (pintype "passive"))
    )
    (net (code "85") (name "/RED2") (class "Default")
      (node (ref "IC13") (pin "3") (pinfunction "QD_3") (pintype "tri_state"))
      (node (ref "PAD_LED") (pin "4") (pinfunction "1_4") (pintype "passive"))
    )
    (net (code "86") (name "/RED3") (class "Default")
      (node (ref "IC13") (pin "6") (pinfunction "QG_6") (pintype "tri_state"))
      (node (ref "PAD_LED") (pin "7") (pinfunction "1_7") (pintype "passive"))
    )
    (net (code "87") (name "/RED4") (class "Default")
      (node (ref "IC11") (pin "1") (pinfunction "QB_1") (pintype "tri_state"))
      (node (ref "PAD_LED") (pin "10") (pinfunction "1_10") (pintype "passive"))
    )
    (net (code "88") (name "/RX") (class "Default")
      (node (ref "B1") (pin "0") (pinfunction "0(RX0)_0") (pintype "bidirectional"))
      (node (ref "CN601") (pin "4") (pinfunction "1_4") (pintype "passive"))
    )
    (net (code "89") (name "/SIDO2") (class "Default")
      (node (ref "IC12") (pin "9") (pinfunction "QH*_9") (pintype "tri_state"))
      (node (ref "IC9") (pin "14") (pinfunction "SER_14") (pintype "input"))
    )
    (net (code "90") (name "/SIDO3") (class "Default")
      (node (ref "IC13") (pin "14") (pinfunction "SER_14") (pintype "input"))
      (node (ref "IC9") (pin "9") (pinfunction "QH*_9") (pintype "tri_state"))
    )
    (net (code "91") (name "/SIDO4") (class "Default")
      (node (ref "IC11") (pin "14") (pinfunction "SER_14") (pintype "input"))
      (node (ref "IC13") (pin "9") (pinfunction "QH*_9") (pintype "tri_state"))
    )
    (net (code "92") (name "/SPKL") (class "Default")
      (node (ref "AUDIOJACK") (pin "4") (pinfunction "4_4") (pintype "passive"))
      (node (ref "AUDIOJACK") (pin "5") (pinfunction "5_5") (pintype "passive"))
      (node (ref "CN131") (pin "3") (pinfunction "1_3") (pintype "passive"))
    )
    (net (code "93") (name "/SPKR") (class "Default")
      (node (ref "AUDIOJACK") (pin "2") (pinfunction "2_2") (pintype "passive"))
      (node (ref "AUDIOJACK") (pin "3") (pinfunction "3_3") (pintype "passive"))
      (node (ref "CN131") (pin "2") (pinfunction "1_2") (pintype "passive"))
    )
    (net (code "94") (name "/SPOT1") (class "Default")
      (node (ref "IC5") (pin "15") (pinfunction "X2_15") (pintype "bidirectional"))
      (node (ref "SPOT1") (pin "2") (pinfunction "1_2") (pintype "passive"))
    )
    (net (code "95") (name "/SPOT2") (class "Default")
      (node (ref "IC5") (pin "12") (pinfunction "X3_12") (pintype "bidirectional"))
      (node (ref "SPOT1") (pin "3") (pinfunction "1_3") (pintype "passive"))
    )
    (net (code "96") (name "/SPOT3") (class "Default")
      (node (ref "IC5") (pin "1") (pinfunction "X4_1") (pintype "bidirectional"))
      (node (ref "SPOT1") (pin "4") (pinfunction "1_4") (pintype "passive"))
    )
    (net (code "97") (name "/SPOT4") (class "Default")
      (node (ref "IC5") (pin "5") (pinfunction "X5_5") (pintype "bidirectional"))
      (node (ref "SPOT2") (pin "2") (pinfunction "1_2") (pintype "passive"))
    )
    (net (code "98") (name "/SPOT5") (class "Default")
      (node (ref "IC5") (pin "2") (pinfunction "X6_2") (pintype "bidirectional"))
      (node (ref "SPOT2") (pin "3") (pinfunction "1_3") (pintype "passive"))
    )
    (net (code "99") (name "/SPOT6") (class "Default")
      (node (ref "IC5") (pin "4") (pinfunction "X7_4") (pintype "bidirectional"))
      (node (ref "SPOT2") (pin "4") (pinfunction "1_4") (pintype "passive"))
    )
    (net (code "100") (name "/SUSTAINPIN") (class "Default")
      (node (ref "CN601") (pin "7") (pinfunction "1_7") (pintype "passive"))
      (node (ref "IC4") (pin "3") (pinfunction "E_3") (pintype "input"))
    )
    (net (code "101") (name "/SWITCH1") (class "Default")
      (node (ref "IC4") (pin "11") (pinfunction "A_11") (pintype "input"))
      (node (ref "PAD_O") (pin "1") (pinfunction "1_1") (pintype "passive"))
    )
    (net (code "102") (name "/SWITCH2") (class "Default")
      (node (ref "IC4") (pin "12") (pinfunction "B_12") (pintype "input"))
      (node (ref "PAD_O") (pin "2") (pinfunction "1_2") (pintype "passive"))
    )
    (net (code "103") (name "/SWITCH3") (class "Default")
      (node (ref "IC4") (pin "13") (pinfunction "C_13") (pintype "input"))
      (node (ref "PAD_O") (pin "3") (pinfunction "1_3") (pintype "passive"))
    )
    (net (code "104") (name "/SWITCH4") (class "Default")
      (node (ref "IC4") (pin "14") (pinfunction "D_14") (pintype "input"))
      (node (ref "PAD_O") (pin "4") (pinfunction "1_4") (pintype "passive"))
    )
    (net (code "105") (name "/SWT_GND1") (class "Default")
      (node (ref "IC9") (pin "15") (pinfunction "QA_15") (pintype "tri_state"))
      (node (ref "PAD_GND") (pin "5") (pinfunction "1_5") (pintype "passive"))
    )
    (net (code "106") (name "/SWT_GND2") (class "Default")
      (node (ref "IC9") (pin "1") (pinfunction "QB_1") (pintype "tri_state"))
      (node (ref "PAD_GND") (pin "6") (pinfunction "1_6") (pintype "passive"))
    )
    (net (code "107") (name "/SWT_GND3") (class "Default")
      (node (ref "IC9") (pin "2") (pinfunction "QC_2") (pintype "tri_state"))
      (node (ref "PAD_GND") (pin "7") (pinfunction "1_7") (pintype "passive"))
    )
    (net (code "108") (name "/SWT_GND4") (class "Default")
      (node (ref "IC9") (pin "3") (pinfunction "QD_3") (pintype "tri_state"))
      (node (ref "PAD_GND") (pin "8") (pinfunction "1_8") (pintype "passive"))
    )
    (net (code "109") (name "/TFT_CS") (class "Default")
      (node (ref "B1") (pin "49") (pinfunction "49_49") (pintype "bidirectional"))
      (node (ref "TFT_DISPLAY") (pin "3") (pinfunction "1_3") (pintype "passive"))
    )
    (net (code "110") (name "/TFT_D{slash}C") (class "Default")
      (node (ref "B1") (pin "48") (pinfunction "48_48") (pintype "bidirectional"))
      (node (ref "TFT_DISPLAY") (pin "5") (pinfunction "1_5") (pintype "passive"))
    )
    (net (code "111") (name "/TFT_RESET") (class "Default")
      (node (ref "B1") (pin "47") (pinfunction "47_47") (pintype "bidirectional"))
      (node (ref "TFT_DISPLAY") (pin "4") (pinfunction "1_4") (pintype "passive"))
    )
    (net (code "112") (name "/TFT_SCK") (class "Default")
      (node (ref "B1") (pin "52") (pinfunction "52_52") (pintype "bidirectional"))
      (node (ref "TFT_DISPLAY") (pin "7") (pinfunction "1_7") (pintype "passive"))
    )
    (net (code "113") (name "/TFT_SDI") (class "Default")
      (node (ref "B1") (pin "51") (pinfunction "51_51") (pintype "bidirectional"))
      (node (ref "TFT_DISPLAY") (pin "6") (pinfunction "1_6") (pintype "passive"))
    )
    (net (code "114") (name "/TFT_SDO") (class "Default")
      (node (ref "B1") (pin "50") (pinfunction "50_50") (pintype "bidirectional"))
      (node (ref "TFT_DISPLAY") (pin "9") (pinfunction "1_9") (pintype "passive"))
    )
    (net (code "115") (name "/TX") (class "Default")
      (node (ref "B1") (pin "1") (pinfunction "1(TX0)_1") (pintype "bidirectional"))
      (node (ref "CN601") (pin "3") (pinfunction "1_3") (pintype "passive"))
    )
    (net (code "116") (name "/T_CLK") (class "Default")
      (node (ref "B1") (pin "25") (pinfunction "25_25") (pintype "bidirectional"))
      (node (ref "TFT_DISPLAY") (pin "10") (pinfunction "1_10") (pintype "passive"))
    )
    (net (code "117") (name "/T_CS") (class "Default")
      (node (ref "B1") (pin "26") (pinfunction "26_26") (pintype "bidirectional"))
      (node (ref "TFT_DISPLAY") (pin "11") (pinfunction "1_11") (pintype "passive"))
    )
    (net (code "118") (name "/T_DIN") (class "Default")
      (node (ref "B1") (pin "27") (pinfunction "27_27") (pintype "bidirectional"))
      (node (ref "TFT_DISPLAY") (pin "12") (pinfunction "1_12") (pintype "passive"))
    )
    (net (code "119") (name "/T_DOUT") (class "Default")
      (node (ref "B1") (pin "29") (pinfunction "29_29") (pintype "bidirectional"))
      (node (ref "TFT_DISPLAY") (pin "13") (pinfunction "1_13") (pintype "passive"))
    )
    (net (code "120") (name "/T_IRQ") (class "Default")
      (node (ref "B1") (pin "30") (pinfunction "30_30") (pintype "bidirectional"))
      (node (ref "TFT_DISPLAY") (pin "14") (pinfunction "1_14") (pintype "passive"))
    )
    (net (code "121") (name "/VIN") (class "Default")
      (node (ref "B1") (pin "VIN") (pinfunction "VIN_VIN") (pintype "bidirectional"))
      (node (ref "C3") (pin "1") (pinfunction "1_1") (pintype "passive"))
      (node (ref "IC10") (pin "OUT") (pinfunction "OUT_OUT") (pintype "passive"))
    )
    (net (code "122") (name "/VIN12V") (class "Default")
      (node (ref "C2") (pin "1") (pinfunction "1_1") (pintype "passive"))
      (node (ref "IC10") (pin "IN") (pinfunction "IN_IN") (pintype "input"))
      (node (ref "POWER") (pin "1") (pinfunction "1_1") (pintype "passive"))
    )
    (net (code "123") (name "/X1_1") (class "Default")
      (node (ref "B1") (pin "A1") (pinfunction "A1(TX0)_A1") (pintype "bidirectional"))
      (node (ref "TOUCH/PAN") (pin "1") (pinfunction "1_1") (pintype "passive"))
    )
    (net (code "124") (name "/X2_1") (class "Default")
      (node (ref "B1") (pin "A2") (pinfunction "A2_A2") (pintype "bidirectional"))
      (node (ref "TOUCH/PAN") (pin "2") (pinfunction "1_2") (pintype "passive"))
    )
    (net (code "125") (name "/Y1_1") (class "Default")
      (node (ref "B1") (pin "A3") (pinfunction "A3_A3") (pintype "bidirectional"))
      (node (ref "TOUCH/PAN") (pin "3") (pinfunction "1_3") (pintype "passive"))
    )
    (net (code "126") (name "/Y2_1") (class "Default")
      (node (ref "B1") (pin "A4") (pinfunction "A4_A4") (pintype "bidirectional"))
      (node (ref "TOUCH/PAN") (pin "4") (pinfunction "1_4") (pintype "passive"))
    )
    (net (code "127") (name "Net-(IC3A-QH)") (class "Default")
      (node (ref "IC3") (pin "9") (pinfunction "QH_9") (pintype "output"))
      (node (ref "IC7") (pin "10") (pinfunction "SER_10") (pintype "input"))
    )
    (net (code "128") (name "Net-(IC12A-SER)") (class "Default")
      (node (ref "IC12") (pin "14") (pinfunction "SER_14") (pintype "input"))
      (node (ref "IC8") (pin "9") (pinfunction "QH*_9") (pintype "tri_state"))
    )
    (net (code "129") (name "unconnected-(B1-18(TX1)-Pad18)") (class "Default")
      (node (ref "B1") (pin "18") (pinfunction "18(TX1)_18") (pintype "bidirectional"))
    )
    (net (code "130") (name "unconnected-(B1-19(RX1)-Pad19)") (class "Default")
      (node (ref "B1") (pin "19") (pinfunction "19(RX1)_19") (pintype "bidirectional"))
    )
    (net (code "131") (name "unconnected-(B1-20(SDA)-Pad20)") (class "Default")
      (node (ref "B1") (pin "20") (pinfunction "20(SDA)_20") (pintype "bidirectional"))
    )
    (net (code "132") (name "unconnected-(B1-21(SCL)-Pad21)") (class "Default")
      (node (ref "B1") (pin "21") (pinfunction "21(SCL)_21") (pintype "bidirectional"))
    )
    (net (code "133") (name "unconnected-(B1-Pad22)") (class "Default")
      (node (ref "B1") (pin "22") (pinfunction "22_22") (pintype "bidirectional"))
    )
    (net (code "134") (name "unconnected-(B1-Pad23)") (class "Default")
      (node (ref "B1") (pin "23") (pinfunction "23_23") (pintype "bidirectional"))
    )
    (net (code "135") (name "unconnected-(B1-Pad24)") (class "Default")
      (node (ref "B1") (pin "24") (pinfunction "24_24") (pintype "bidirectional"))
    )
    (net (code "136") (name "unconnected-(B1-Pad28)") (class "Default")
      (node (ref "B1") (pin "28") (pinfunction "28_28") (pintype "bidirectional"))
    )
    (net (code "137") (name "unconnected-(B1-Pad31)") (class "Default")
      (node (ref "B1") (pin "31") (pinfunction "31_31") (pintype "bidirectional"))
    )
    (net (code "138") (name "unconnected-(B1-Pad32)") (class "Default")
      (node (ref "B1") (pin "32") (pinfunction "32_32") (pintype "bidirectional"))
    )
    (net (code "139") (name "unconnected-(B1-Pad33)") (class "Default")
      (node (ref "B1") (pin "33") (pinfunction "33_33") (pintype "bidirectional"))
    )
    (net (code "140") (name "unconnected-(B1-Pad34)") (class "Default")
      (node (ref "B1") (pin "34") (pinfunction "34_34") (pintype "bidirectional"))
    )
    (net (code "141") (name "unconnected-(B1-Pad35)") (class "Default")
      (node (ref "B1") (pin "35") (pinfunction "35_35") (pintype "bidirectional"))
    )
    (net (code "142") (name "unconnected-(B1-Pad36)") (class "Default")
      (node (ref "B1") (pin "36") (pinfunction "36_36") (pintype "bidirectional"))
    )
    (net (code "143") (name "unconnected-(B1-Pad37)") (class "Default")
      (node (ref "B1") (pin "37") (pinfunction "37_37") (pintype "bidirectional"))
    )
    (net (code "144") (name "unconnected-(B1-Pad38)") (class "Default")
      (node (ref "B1") (pin "38") (pinfunction "38_38") (pintype "bidirectional"))
    )
    (net (code "145") (name "unconnected-(B1-Pad39)") (class "Default")
      (node (ref "B1") (pin "39") (pinfunction "39_39") (pintype "bidirectional"))
    )
    (net (code "146") (name "unconnected-(B1-Pad40)") (class "Default")
      (node (ref "B1") (pin "40") (pinfunction "40_40") (pintype "bidirectional"))
    )
    (net (code "147") (name "unconnected-(B1-Pad41)") (class "Default")
      (node (ref "B1") (pin "41") (pinfunction "41_41") (pintype "bidirectional"))
    )
    (net (code "148") (name "unconnected-(B1-Pad42)") (class "Default")
      (node (ref "B1") (pin "42") (pinfunction "42_42") (pintype "bidirectional"))
    )
    (net (code "149") (name "unconnected-(B1-Pad43)") (class "Default")
      (node (ref "B1") (pin "43") (pinfunction "43_43") (pintype "bidirectional"))
    )
    (net (code "150") (name "unconnected-(B1-Pad44)") (class "Default")
      (node (ref "B1") (pin "44") (pinfunction "44_44") (pintype "bidirectional"))
    )
    (net (code "151") (name "unconnected-(B1-Pad45)") (class "Default")
      (node (ref "B1") (pin "45") (pinfunction "45_45") (pintype "bidirectional"))
    )
    (net (code "152") (name "unconnected-(B1-Pad46)") (class "Default")
      (node (ref "B1") (pin "46") (pinfunction "46_46") (pintype "bidirectional"))
    )
    (net (code "153") (name "unconnected-(B1-Pad53)") (class "Default")
      (node (ref "B1") (pin "53") (pinfunction "53_53") (pintype "bidirectional"))
    )
    (net (code "154") (name "unconnected-(B1-PadA6)") (class "Default")
      (node (ref "B1") (pin "A6") (pinfunction "A6_A6") (pintype "bidirectional"))
    )
    (net (code "155") (name "unconnected-(B1-PadA7)") (class "Default")
      (node (ref "B1") (pin "A7") (pinfunction "A7_A7") (pintype "bidirectional"))
    )
    (net (code "156") (name "unconnected-(B1-PadA8)") (class "Default")
      (node (ref "B1") (pin "A8") (pinfunction "A8_A8") (pintype "bidirectional"))
    )
    (net (code "157") (name "unconnected-(B1-PadA9)") (class "Default")
      (node (ref "B1") (pin "A9") (pinfunction "A9_A9") (pintype "bidirectional"))
    )
    (net (code "158") (name "unconnected-(B1-PadA10)") (class "Default")
      (node (ref "B1") (pin "A10") (pinfunction "A10_A10") (pintype "bidirectional"))
    )
    (net (code "159") (name "unconnected-(B1-PadA11)") (class "Default")
      (node (ref "B1") (pin "A11") (pinfunction "A11_A11") (pintype "bidirectional"))
    )
    (net (code "160") (name "unconnected-(B1-PadA12)") (class "Default")
      (node (ref "B1") (pin "A12") (pinfunction "A12_A12") (pintype "bidirectional"))
    )
    (net (code "161") (name "unconnected-(B1-PadA13)") (class "Default")
      (node (ref "B1") (pin "A13") (pinfunction "A13_A13") (pintype "bidirectional"))
    )
    (net (code "162") (name "unconnected-(B1-PadA14)") (class "Default")
      (node (ref "B1") (pin "A14") (pinfunction "A14_A14") (pintype "bidirectional"))
    )
    (net (code "163") (name "unconnected-(B1-PadA15)") (class "Default")
      (node (ref "B1") (pin "A15") (pinfunction "A15_A15") (pintype "bidirectional"))
    )
    (net (code "164") (name "unconnected-(B1-PadAREF)") (class "Default")
      (node (ref "B1") (pin "AREF") (pinfunction "AREF_AREF") (pintype "bidirectional"))
    )
    (net (code "165") (name "unconnected-(B1-PadRESET)") (class "Default")
      (node (ref "B1") (pin "RESET") (pinfunction "RESET_RESET") (pintype "bidirectional"))
    )
    (net (code "166") (name "unconnected-(CN131B-1-Pad10)") (class "Default")
      (node (ref "CN131") (pin "10") (pinfunction "1_10") (pintype "passive"))
    )
    (net (code "167") (name "unconnected-(CN131F-1-Pad4)") (class "Default")
      (node (ref "CN131") (pin "4") (pinfunction "1_4") (pintype "passive"))
    )
    (net (code "168") (name "unconnected-(CN131G-1-Pad5)") (class "Default")
      (node (ref "CN131") (pin "5") (pinfunction "1_5") (pintype "passive"))
    )
    (net (code "169") (name "unconnected-(CN131I-1-Pad7)") (class "Default")
      (node (ref "CN131") (pin "7") (pinfunction "1_7") (pintype "passive"))
    )
    (net (code "170") (name "unconnected-(CN131J-1-Pad8)") (class "Default")
      (node (ref "CN131") (pin "8") (pinfunction "1_8") (pintype "passive"))
    )
    (net (code "171") (name "unconnected-(CN531-Pad1)") (class "Default")
      (node (ref "CN531") (pin "1") (pinfunction "1_1") (pintype "passive"))
    )
    (net (code "172") (name "unconnected-(CN531E-1-Pad13)") (class "Default")
      (node (ref "CN531") (pin "13") (pinfunction "1_13") (pintype "passive"))
    )
    (net (code "173") (name "unconnected-(CN531F-1-Pad14)") (class "Default")
      (node (ref "CN531") (pin "14") (pinfunction "1_14") (pintype "passive"))
    )
    (net (code "174") (name "unconnected-(CN531G-1-Pad15)") (class "Default")
      (node (ref "CN531") (pin "15") (pinfunction "1_15") (pintype "passive"))
    )
    (net (code "175") (name "unconnected-(CN531H-1-Pad16)") (class "Default")
      (node (ref "CN531") (pin "16") (pinfunction "1_16") (pintype "passive"))
    )
    (net (code "176") (name "unconnected-(CN531I-1-Pad2)") (class "Default")
      (node (ref "CN531") (pin "2") (pinfunction "1_2") (pintype "passive"))
    )
    (net (code "177") (name "unconnected-(CN531J-1-Pad3)") (class "Default")
      (node (ref "CN531") (pin "3") (pinfunction "1_3") (pintype "passive"))
    )
    (net (code "178") (name "unconnected-(CN531K-1-Pad4)") (class "Default")
      (node (ref "CN531") (pin "4") (pinfunction "1_4") (pintype "passive"))
    )
    (net (code "179") (name "unconnected-(CN531L-1-Pad5)") (class "Default")
      (node (ref "CN531") (pin "5") (pinfunction "1_5") (pintype "passive"))
    )
    (net (code "180") (name "unconnected-(CN601-Pad1)") (class "Default")
      (node (ref "CN601") (pin "1") (pinfunction "1_1") (pintype "passive"))
    )
    (net (code "181") (name "unconnected-(CN601B-1-Pad2)") (class "Default")
      (node (ref "CN601") (pin "2") (pinfunction "1_2") (pintype "passive"))
    )
    (net (code "182") (name "unconnected-(IC3A-SER-Pad10)") (class "Default")
      (node (ref "IC3") (pin "10") (pinfunction "SER_10") (pintype "input"))
    )
    (net (code "183") (name "unconnected-(IC3A-~{QH}-Pad7)") (class "Default")
      (node (ref "IC3") (pin "7") (pinfunction "~{QH}_7") (pintype "output"))
    )
    (net (code "184") (name "unconnected-(IC4A-~{QH}-Pad7)") (class "Default")
      (node (ref "IC4") (pin "7") (pinfunction "~{QH}_7") (pintype "output"))
    )
    (net (code "185") (name "unconnected-(IC7A-~{QH}-Pad7)") (class "Default")
      (node (ref "IC7") (pin "7") (pinfunction "~{QH}_7") (pintype "output"))
    )
    (net (code "186") (name "unconnected-(IC11A-QH*-Pad9)") (class "Default")
      (node (ref "IC11") (pin "9") (pinfunction "QH*_9") (pintype "tri_state"))
    )
    (net (code "187") (name "unconnected-(IC12A-QH-Pad7)") (class "Default")
      (node (ref "IC12") (pin "7") (pinfunction "QH_7") (pintype "tri_state"))
    )
  )
)
